# 00_McuComBrd.net
KiCad netlist of a schematic drawn in Altium Designer
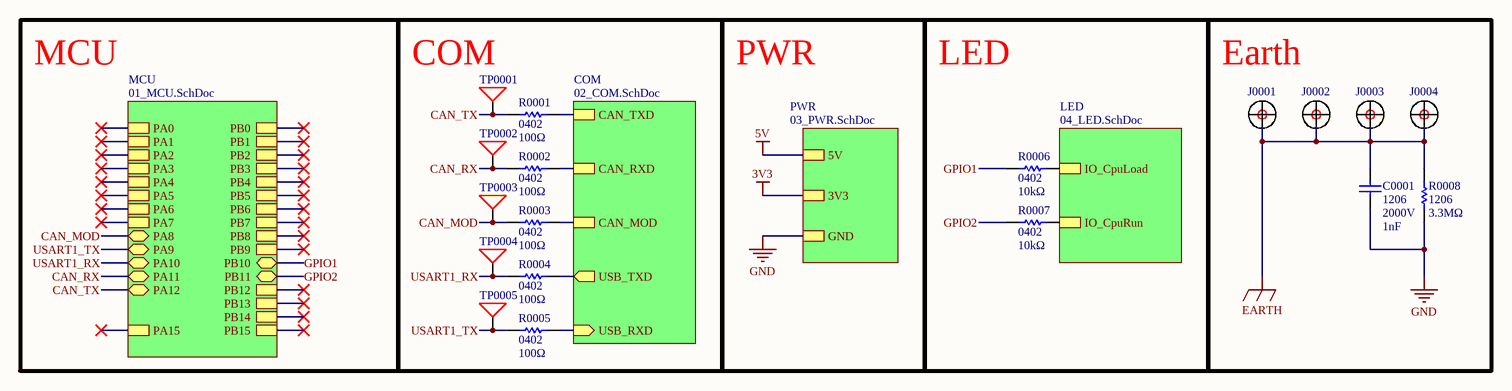
[diagram p0: 00_McuComBrd.SchDoc]

(export (version "E")
  (design (tool "Eeschema 10.0.6"))
  (components
    (comp (ref "C0001")
      (value "Cap")
      (footprint "C1206")
      (description "电容")
      (fields (field (name "SIZE") "1206") (field (name "VOLT") "2000V") (field (name "CAP") "1nF"))
      (libsource (lib "LCR") (part "Cap"))
    )
    (comp (ref "J0001") (value "HOLE") (footprint "定位孔 Φ3 1") (libsource (lib "Interface") (part "HOLE")))
    (comp (ref "J0002") (value "HOLE") (footprint "定位孔 Φ3 1") (libsource (lib "Interface") (part "HOLE")))
    (comp (ref "J0003") (value "HOLE") (footprint "定位孔 Φ3 1") (libsource (lib "Interface") (part "HOLE")))
    (comp (ref "J0004") (value "HOLE") (footprint "定位孔 Φ3 1") (libsource (lib "Interface") (part "HOLE")))
    (comp (ref "R0001")
      (value "RES")
      (footprint "R0402")
      (description "电阻")
      (fields (field (name "SIZE") "0402") (field (name "RES") "100Ω"))
      (libsource (lib "LCR") (part "RES"))
    )
    (comp (ref "R0002")
      (value "RES")
      (footprint "R0402")
      (description "电阻")
      (fields (field (name "SIZE") "0402") (field (name "RES") "100Ω"))
      (libsource (lib "LCR") (part "RES"))
    )
    (comp (ref "R0003")
      (value "RES")
      (footprint "R0402")
      (description "电阻")
      (fields (field (name "SIZE") "0402") (field (name "RES") "100Ω"))
      (libsource (lib "LCR") (part "RES"))
    )
    (comp (ref "R0004")
      (value "RES")
      (footprint "R0402")
      (description "电阻")
      (fields (field (name "SIZE") "0402") (field (name "RES") "100Ω"))
      (libsource (lib "LCR") (part "RES"))
    )
    (comp (ref "R0005")
      (value "RES")
      (footprint "R0402")
      (description "电阻")
      (fields (field (name "SIZE") "0402") (field (name "RES") "100Ω"))
      (libsource (lib "LCR") (part "RES"))
    )
    (comp (ref "R0006")
      (value "RES")
      (footprint "R0402")
      (description "电阻")
      (fields (field (name "SIZE") "0402") (field (name "RES") "10kΩ"))
      (libsource (lib "LCR") (part "RES"))
    )
    (comp (ref "R0007")
      (value "RES")
      (footprint "R0402")
      (description "电阻")
      (fields (field (name "SIZE") "0402") (field (name "RES") "10kΩ"))
      (libsource (lib "LCR") (part "RES"))
    )
    (comp (ref "R0008")
      (value "RES")
      (footprint "R1206")
      (description "电阻")
      (fields (field (name "SIZE") "1206") (field (name "RES") "3.3MΩ"))
      (libsource (lib "LCR") (part "RES"))
    )
    (comp (ref "TP0001")
      (value "Test Point")
      (footprint "Test Point")
      (libsource (lib "Interface") (part "Test Point"))
    )
    (comp (ref "TP0002")
      (value "Test Point")
      (footprint "Test Point")
      (libsource (lib "Interface") (part "Test Point"))
    )
    (comp (ref "TP0003")
      (value "Test Point")
      (footprint "Test Point")
      (libsource (lib "Interface") (part "Test Point"))
    )
    (comp (ref "TP0004")
      (value "Test Point")
      (footprint "Test Point")
      (libsource (lib "Interface") (part "Test Point"))
    )
    (comp (ref "TP0005")
      (value "Test Point")
      (footprint "Test Point")
      (libsource (lib "Interface") (part "Test Point"))
    )
  )
  (nets
    (net (code "1") (name "/CAN_MOD") (class "Default")
      (node (ref "R0003") (pin "1") (pinfunction "1_1") (pintype "passive"))
      (node (ref "TP0003") (pin "1") (pinfunction "1_1") (pintype "passive"))
    )
    (net (code "2") (name "/CAN_MOD_1") (class "Default")
      (node (ref "R0003") (pin "2") (pinfunction "2_2") (pintype "passive"))
    )
    (net (code "3") (name "/CAN_RX") (class "Default")
      (node (ref "R0002") (pin "1") (pinfunction "1_1") (pintype "passive"))
      (node (ref "TP0002") (pin "1") (pinfunction "1_1") (pintype "passive"))
    )
    (net (code "4") (name "/CAN_RXD") (class "Default")
      (node (ref "R0002") (pin "2") (pinfunction "2_2") (pintype "passive"))
    )
    (net (code "5") (name "/CAN_TX") (class "Default")
      (node (ref "R0001") (pin "1") (pinfunction "1_1") (pintype "passive"))
      (node (ref "TP0001") (pin "1") (pinfunction "1_1") (pintype "passive"))
    )
    (net (code "6") (name "/CAN_TXD") (class "Default")
      (node (ref "R0001") (pin "2") (pinfunction "2_2") (pintype "passive"))
    )
    (net (code "7") (name "/GPIO1") (class "Default")
      (node (ref "R0006") (pin "1") (pinfunction "1_1") (pintype "passive"))
    )
    (net (code "8") (name "/GPIO2") (class "Default")
      (node (ref "R0007") (pin "1") (pinfunction "1_1") (pintype "passive"))
    )
    (net (code "9") (name "/IO_CpuLoad") (class "Default")
      (node (ref "R0006") (pin "2") (pinfunction "2_2") (pintype "passive"))
    )
    (net (code "10") (name "/IO_CpuRun") (class "Default")
      (node (ref "R0007") (pin "2") (pinfunction "2_2") (pintype "passive"))
    )
    (net (code "34") (name "/USART1_RX") (class "Default")
      (node (ref "R0004") (pin "1") (pinfunction "1_1") (pintype "passive"))
      (node (ref "TP0004") (pin "1") (pinfunction "1_1") (pintype "passive"))
    )
    (net (code "35") (name "/USART1_TX") (class "Default")
      (node (ref "R0005") (pin "1") (pinfunction "1_1") (pintype "passive"))
      (node (ref "TP0005") (pin "1") (pinfunction "1_1") (pintype "passive"))
    )
    (net (code "36") (name "/USB_RXD") (class "Default")
      (node (ref "R0005") (pin "2") (pinfunction "2_2") (pintype "passive"))
    )
    (net (code "37") (name "/USB_TXD") (class "Default")
      (node (ref "R0004") (pin "2") (pinfunction "2_2") (pintype "passive"))
    )
    (net (code "40") (name "EARTH") (class "Default")
      (node (ref "C0001") (pin "2") (pinfunction "2_2") (pintype "passive"))
      (node (ref "J0001") (pin "1") (pintype "passive"))
      (node (ref "J0002") (pin "1") (pintype "passive"))
      (node (ref "J0003") (pin "1") (pintype "passive"))
      (node (ref "J0004") (pin "1") (pintype "passive"))
      (node (ref "R0008") (pin "2") (pinfunction "2_2") (pintype "passive"))
    )
    (net (code "41") (name "GND") (class "Default")
      (node (ref "C0001") (pin "1") (pinfunction "1_1") (pintype "passive"))
      (node (ref "R0008") (pin "1") (pinfunction "1_1") (pintype "passive"))
    )
  )
)
